# test3.net
KiCad netlist of a schematic drawn in EAGLE
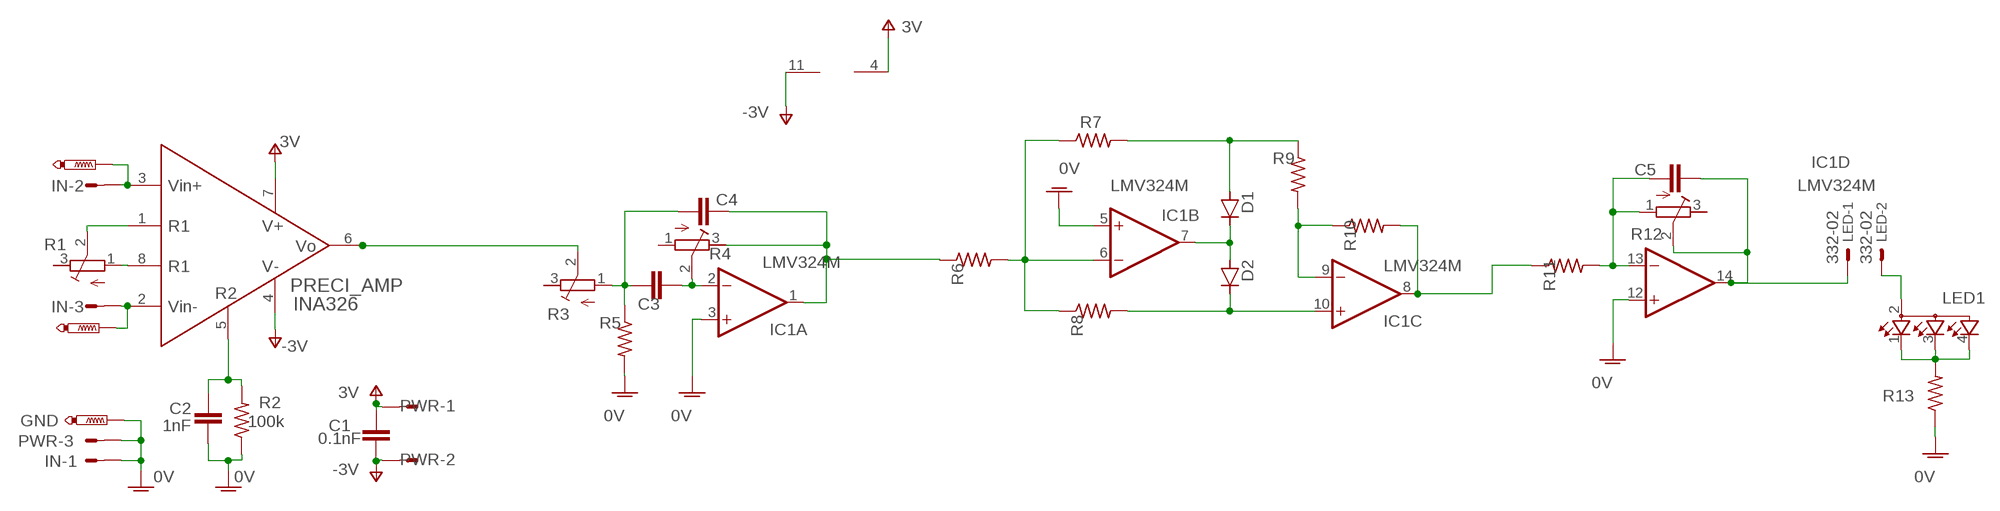
[diagram p0: schematic, sheet 1]

(export (version "E")
  (design (tool "Eeschema 10.0.6"))
  (components
    (comp (ref "C1")
      (value "0.1nF")
      (footprint "eagle-import:C0603")
      (libsource (lib "eagle-import") (part "C-EUC0603"))
    )
    (comp (ref "C2")
      (value "1nF")
      (footprint "eagle-import:C0603")
      (libsource (lib "eagle-import") (part "C-EUC0603"))
    )
    (comp (ref "C3")
      (value "0.1nF")
      (footprint "eagle-import:C0603")
      (libsource (lib "eagle-import") (part "C-EUC0603"))
    )
    (comp (ref "C4")
      (value "0.1nF")
      (footprint "eagle-import:C0603")
      (libsource (lib "eagle-import") (part "C-EUC0603"))
    )
    (comp (ref "C5")
      (value "0.1nF")
      (footprint "eagle-import:C0603")
      (libsource (lib "eagle-import") (part "C-EUC0603"))
    )
    (comp (ref "D1")
      (value "D-SOD-80")
      (footprint "eagle-import:SOD80")
      (libsource (lib "eagle-import") (part "D-SOD-80"))
    )
    (comp (ref "D2")
      (value "D-SOD-80")
      (footprint "eagle-import:SOD80")
      (libsource (lib "eagle-import") (part "D-SOD-80"))
    )
    (comp (ref "GND")
      (value "PTR1PAD1-13")
      (footprint "eagle-import:P1-13")
      (libsource (lib "eagle-import") (part "PTR1PAD1-13"))
    )
    (comp (ref "IC1")
      (value "LMV324M")
      (footprint "eagle-import:SO14")
      (fields (field (name "SPICEPREFIX") "J"))
      (libsource (lib "eagle-import") (part "LMV324?M"))
    )
    (comp (ref "IN")
      (value "MT6-3")
      (footprint "eagle-import:MT6-3")
      (libsource (lib "eagle-import") (part "MT6-3"))
    )
    (comp (ref "IN+")
      (value "PTR1PAD1-13")
      (footprint "eagle-import:P1-13")
      (libsource (lib "eagle-import") (part "PTR1PAD1-13"))
    )
    (comp (ref "IN-")
      (value "PTR1PAD1-13")
      (footprint "eagle-import:P1-13")
      (libsource (lib "eagle-import") (part "PTR1PAD1-13"))
    )
    (comp (ref "LED")
      (value "332-02")
      (footprint "eagle-import:332-02")
      (libsource (lib "eagle-import") (part "332-02"))
    )
    (comp (ref "LED1")
      (value "TOPLED-3")
      (footprint "eagle-import:P-LCC-4-3")
      (libsource (lib "eagle-import") (part "TOPLED-3"))
    )
    (comp (ref "PRECI_AMP")
      (value "INA326")
      (footprint "eagle-import:SOP65P490X110-8N")
      (fields
        (field (name "DIGI-KEY_PART_NUMBER") "296-15312-1-ND")
        (field (name "MF") "Texas Instruments")
        (field (name "MP") "INA326EA/250")
        (field (name "MP_1") "INA326")
      )
      (libsource (lib "eagle-import") (part "INA326EA/250"))
    )
    (comp (ref "PWR")
      (value "MT6-3")
      (footprint "eagle-import:MT6-3")
      (libsource (lib "eagle-import") (part "MT6-3"))
    )
    (comp (ref "R1")
      (value "R-TRIMM4G/J")
      (footprint "eagle-import:RTRIM4G_J")
      (libsource (lib "eagle-import") (part "R-TRIMM4G/J"))
    )
    (comp (ref "R2")
      (value "100k")
      (footprint "eagle-import:R0603")
      (libsource (lib "eagle-import") (part "R-US_R0603"))
    )
    (comp (ref "R3")
      (value "R-TRIMM4G/J")
      (footprint "eagle-import:RTRIM4G_J")
      (libsource (lib "eagle-import") (part "R-TRIMM4G/J"))
    )
    (comp (ref "R4")
      (value "R-TRIMM4G/J")
      (footprint "eagle-import:RTRIM4G_J")
      (libsource (lib "eagle-import") (part "R-TRIMM4G/J"))
    )
    (comp (ref "R5")
      (value "100k")
      (footprint "eagle-import:R0603")
      (libsource (lib "eagle-import") (part "R-US_R0603"))
    )
    (comp (ref "R6")
      (value "100k")
      (footprint "eagle-import:R0603")
      (libsource (lib "eagle-import") (part "R-US_R0603"))
    )
    (comp (ref "R7")
      (value "100k")
      (footprint "eagle-import:R0603")
      (libsource (lib "eagle-import") (part "R-US_R0603"))
    )
    (comp (ref "R8")
      (value "100k")
      (footprint "eagle-import:R0603")
      (libsource (lib "eagle-import") (part "R-US_R0603"))
    )
    (comp (ref "R9")
      (value "100k")
      (footprint "eagle-import:R0603")
      (libsource (lib "eagle-import") (part "R-US_R0603"))
    )
    (comp (ref "R10")
      (value "100k")
      (footprint "eagle-import:R0603")
      (libsource (lib "eagle-import") (part "R-US_R0603"))
    )
    (comp (ref "R11")
      (value "100k")
      (footprint "eagle-import:R0603")
      (libsource (lib "eagle-import") (part "R-US_R0603"))
    )
    (comp (ref "R12")
      (value "R-TRIMM4G/J")
      (footprint "eagle-import:RTRIM4G_J")
      (libsource (lib "eagle-import") (part "R-TRIMM4G/J"))
    )
    (comp (ref "R13")
      (value "100k")
      (footprint "eagle-import:R0603")
      (libsource (lib "eagle-import") (part "R-US_R0603"))
    )
  )
  (nets
    (net (code "1") (name "-3V") (class "Default")
      (node (ref "C1") (pin "2") (pinfunction "2_2") (pintype "passive"))
      (node (ref "IC1") (pin "11") (pinfunction "V-_11") (pintype "power_in"))
      (node (ref "PRECI_AMP") (pin "4") (pinfunction "V-_4") (pintype "power_in"))
      (node (ref "PWR") (pin "2") (pinfunction "S_2") (pintype "passive"))
    )
    (net (code "2") (name "0V") (class "Default")
      (node (ref "C2") (pin "1") (pinfunction "1_1") (pintype "passive"))
      (node (ref "GND") (pin "TP") (pinfunction "TP_TP") (pintype "input"))
      (node (ref "IC1") (pin "12") (pinfunction "+IN_12") (pintype "input"))
      (node (ref "IC1") (pin "3") (pinfunction "+IN_3") (pintype "input"))
      (node (ref "IC1") (pin "5") (pinfunction "+IN_5") (pintype "input"))
      (node (ref "IN") (pin "1") (pinfunction "S_1") (pintype "passive"))
      (node (ref "PWR") (pin "3") (pinfunction "S_3") (pintype "passive"))
      (node (ref "R13") (pin "1") (pinfunction "1_1") (pintype "passive"))
      (node (ref "R2") (pin "1") (pinfunction "1_1") (pintype "passive"))
      (node (ref "R5") (pin "2") (pinfunction "2_2") (pintype "passive"))
    )
    (net (code "3") (name "3V") (class "Default")
      (node (ref "C1") (pin "1") (pinfunction "1_1") (pintype "passive"))
      (node (ref "IC1") (pin "4") (pinfunction "V+_4") (pintype "power_in"))
      (node (ref "PRECI_AMP") (pin "7") (pinfunction "V+_7") (pintype "power_in"))
      (node (ref "PWR") (pin "1") (pinfunction "S_1") (pintype "passive"))
    )
    (net (code "4") (name "Net-(D1-A)") (class "Default")
      (node (ref "D1") (pin "2") (pinfunction "A_2") (pintype "passive"))
      (node (ref "R7") (pin "2") (pinfunction "2_2") (pintype "passive"))
      (node (ref "R9") (pin "1") (pinfunction "1_1") (pintype "passive"))
    )
    (net (code "5") (name "Net-(D1-C)") (class "Default")
      (node (ref "D1") (pin "1") (pinfunction "C_1") (pintype "passive"))
      (node (ref "D2") (pin "2") (pinfunction "A_2") (pintype "passive"))
      (node (ref "IC1") (pin "7") (pinfunction "OUT_7") (pintype "output"))
    )
    (net (code "6") (name "Net-(D2-C)") (class "Default")
      (node (ref "D2") (pin "1") (pinfunction "C_1") (pintype "passive"))
      (node (ref "IC1") (pin "10") (pinfunction "+IN_10") (pintype "input"))
      (node (ref "R8") (pin "2") (pinfunction "2_2") (pintype "passive"))
    )
    (net (code "7") (name "Net-(IC1A--IN)") (class "Default")
      (node (ref "C3") (pin "1") (pinfunction "1_1") (pintype "passive"))
      (node (ref "IC1") (pin "2") (pinfunction "-IN_2") (pintype "input"))
      (node (ref "R4") (pin "2") (pinfunction "S_2") (pintype "passive"))
    )
    (net (code "8") (name "Net-(IC1A-OUT)") (class "Default")
      (node (ref "C4") (pin "1") (pinfunction "1_1") (pintype "passive"))
      (node (ref "IC1") (pin "1") (pinfunction "OUT_1") (pintype "output"))
      (node (ref "R4") (pin "3") (pinfunction "E_3") (pintype "passive"))
      (node (ref "R6") (pin "1") (pinfunction "1_1") (pintype "passive"))
    )
    (net (code "9") (name "Net-(IC1B--IN)") (class "Default")
      (node (ref "IC1") (pin "6") (pinfunction "-IN_6") (pintype "input"))
      (node (ref "R6") (pin "2") (pinfunction "2_2") (pintype "passive"))
      (node (ref "R7") (pin "1") (pinfunction "1_1") (pintype "passive"))
      (node (ref "R8") (pin "1") (pinfunction "1_1") (pintype "passive"))
    )
    (net (code "10") (name "Net-(IC1C--IN)") (class "Default")
      (node (ref "IC1") (pin "9") (pinfunction "-IN_9") (pintype "input"))
      (node (ref "R10") (pin "1") (pinfunction "1_1") (pintype "passive"))
      (node (ref "R9") (pin "2") (pinfunction "2_2") (pintype "passive"))
    )
    (net (code "11") (name "Net-(IC1C-OUT)") (class "Default")
      (node (ref "IC1") (pin "8") (pinfunction "OUT_8") (pintype "output"))
      (node (ref "R10") (pin "2") (pinfunction "2_2") (pintype "passive"))
      (node (ref "R11") (pin "1") (pinfunction "1_1") (pintype "passive"))
    )
    (net (code "12") (name "Net-(IC1D--IN)") (class "Default")
      (node (ref "C5") (pin "1") (pinfunction "1_1") (pintype "passive"))
      (node (ref "IC1") (pin "13") (pinfunction "-IN_13") (pintype "input"))
      (node (ref "R11") (pin "2") (pinfunction "2_2") (pintype "passive"))
      (node (ref "R12") (pin "1") (pinfunction "A_1") (pintype "passive"))
    )
    (net (code "13") (name "Net-(IC1D-OUT)") (class "Default")
      (node (ref "C5") (pin "2") (pinfunction "2_2") (pintype "passive"))
      (node (ref "IC1") (pin "14") (pinfunction "OUT_14") (pintype "output"))
      (node (ref "LED") (pin "1") (pinfunction "S_1") (pintype "passive"))
      (node (ref "R12") (pin "2") (pinfunction "S_2") (pintype "passive"))
    )
    (net (code "14") (name "Net-(INB-S)") (class "Default")
      (node (ref "IN") (pin "2") (pinfunction "S_2") (pintype "passive"))
      (node (ref "IN+") (pin "TP") (pinfunction "TP_TP") (pintype "input"))
      (node (ref "PRECI_AMP") (pin "3") (pinfunction "VIN+_3") (pintype "input"))
    )
    (net (code "15") (name "Net-(INC-S)") (class "Default")
      (node (ref "IN") (pin "3") (pinfunction "S_3") (pintype "passive"))
      (node (ref "IN-") (pin "TP") (pinfunction "TP_TP") (pintype "input"))
      (node (ref "PRECI_AMP") (pin "2") (pinfunction "VIN-_2") (pintype "input"))
    )
    (net (code "16") (name "Net-(LED1-A2)") (class "Default")
      (node (ref "LED") (pin "2") (pinfunction "S_2") (pintype "passive"))
      (node (ref "LED1") (pin "2") (pinfunction "A2_2") (pintype "passive"))
    )
    (net (code "17") (name "Net-(LED1-CBLUE)") (class "Default")
      (node (ref "LED1") (pin "1") (pinfunction "CRED_1") (pintype "passive"))
      (node (ref "LED1") (pin "3") (pinfunction "CBLUE_3") (pintype "passive"))
      (node (ref "LED1") (pin "4") (pinfunction "CGREEN_4") (pintype "passive"))
      (node (ref "R13") (pin "2") (pinfunction "2_2") (pintype "passive"))
    )
    (net (code "18") (name "Net-(PRECI_AMP-R1)") (class "Default")
      (node (ref "PRECI_AMP") (pin "8") (pinfunction "R1_8") (pintype "input"))
      (node (ref "R1") (pin "1") (pinfunction "A_1") (pintype "passive"))
    )
    (net (code "19") (name "Net-(PRECI_AMP-R1_2)") (class "Default")
      (node (ref "PRECI_AMP") (pin "1") (pinfunction "R1_2_1") (pintype "input"))
      (node (ref "R1") (pin "2") (pinfunction "S_2") (pintype "passive"))
    )
    (net (code "20") (name "Net-(PRECI_AMP-R2)") (class "Default")
      (node (ref "C2") (pin "2") (pinfunction "2_2") (pintype "passive"))
      (node (ref "PRECI_AMP") (pin "5") (pinfunction "R2_5") (pintype "input"))
      (node (ref "R2") (pin "2") (pinfunction "2_2") (pintype "passive"))
    )
    (net (code "21") (name "Net-(PRECI_AMP-VO)") (class "Default")
      (node (ref "PRECI_AMP") (pin "6") (pinfunction "VO_6") (pintype "output"))
      (node (ref "R3") (pin "2") (pinfunction "S_2") (pintype "passive"))
    )
    (net (code "22") (name "Net-(R3-A)") (class "Default")
      (node (ref "C3") (pin "2") (pinfunction "2_2") (pintype "passive"))
      (node (ref "C4") (pin "2") (pinfunction "2_2") (pintype "passive"))
      (node (ref "R3") (pin "1") (pinfunction "A_1") (pintype "passive"))
      (node (ref "R5") (pin "1") (pinfunction "1_1") (pintype "passive"))
    )
    (net (code "23") (name "unconnected-(R1-E-Pad3)") (class "Default")
      (node (ref "R1") (pin "3") (pinfunction "E_3") (pintype "passive"))
    )
    (net (code "24") (name "unconnected-(R3-E-Pad3)") (class "Default")
      (node (ref "R3") (pin "3") (pinfunction "E_3") (pintype "passive"))
    )
    (net (code "25") (name "unconnected-(R4-A-Pad1)") (class "Default")
      (node (ref "R4") (pin "1") (pinfunction "A_1") (pintype "passive"))
    )
    (net (code "26") (name "unconnected-(R12-E-Pad3)") (class "Default")
      (node (ref "R12") (pin "3") (pinfunction "E_3") (pintype "passive"))
    )
  )
)
